# esp-12-f-breakout-ch340g.net
KiCad netlist of a schematic drawn in EAGLE
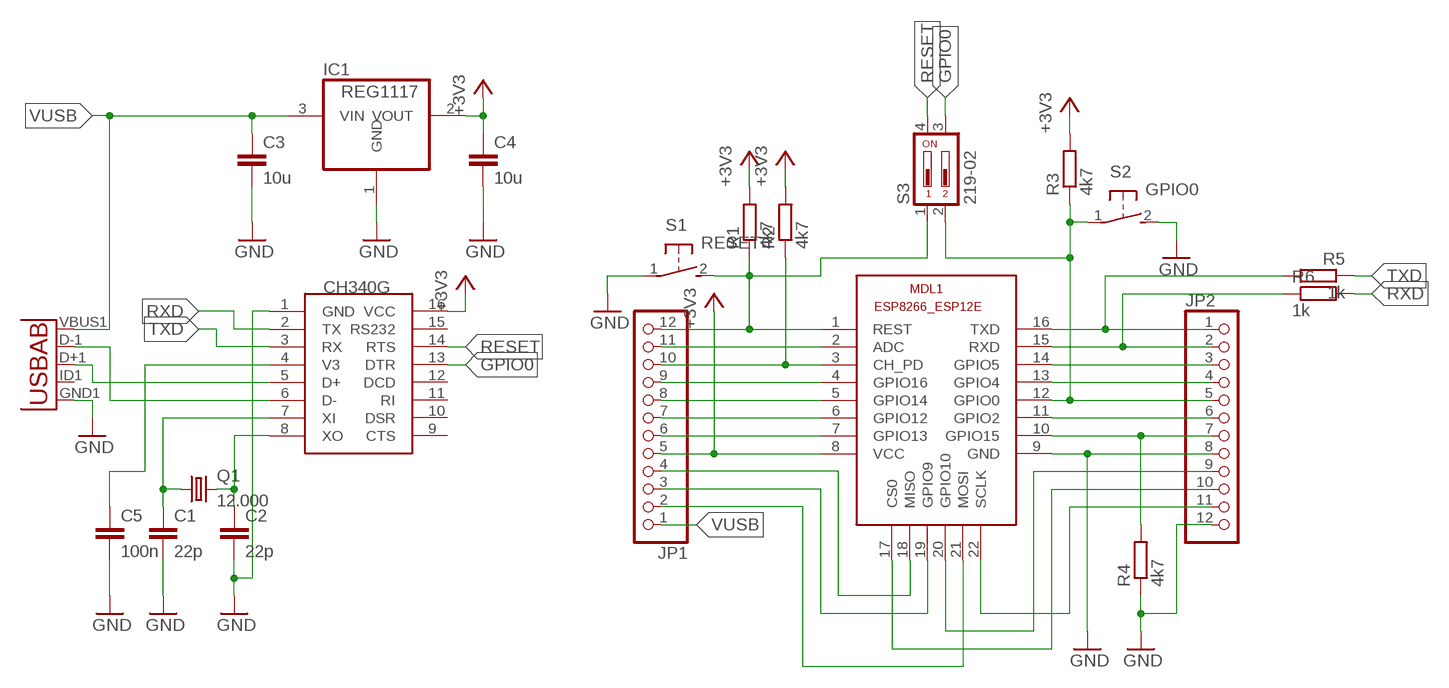
[diagram p0: schematic, sheet 1]

(export (version "E")
  (design (tool "Eeschema 10.0.6"))
  (components
    (comp (ref "C1")
      (value "22p")
      (footprint "eagle-import:C0805")
      (libsource (lib "eagle-import") (part "C-EUC0805"))
    )
    (comp (ref "C2")
      (value "22p")
      (footprint "eagle-import:C0805")
      (libsource (lib "eagle-import") (part "C-EUC0805"))
    )
    (comp (ref "C3")
      (value "10u")
      (footprint "eagle-import:C0805")
      (libsource (lib "eagle-import") (part "C-EUC0805"))
    )
    (comp (ref "C4")
      (value "10u")
      (footprint "eagle-import:C0805")
      (libsource (lib "eagle-import") (part "C-EUC0805"))
    )
    (comp (ref "C5")
      (value "100n")
      (footprint "eagle-import:C0805")
      (libsource (lib "eagle-import") (part "C-EUC0805"))
    )
    (comp (ref "IC1")
      (value "REG1117")
      (footprint "eagle-import:SOT223")
      (libsource (lib "eagle-import") (part "REG1117"))
    )
    (comp (ref "JP1")
      (value "PINHD-1X12")
      (footprint "eagle-import:1X12")
      (libsource (lib "eagle-import") (part "PINHD-1X12"))
    )
    (comp (ref "JP2")
      (value "PINHD-1X12")
      (footprint "eagle-import:1X12")
      (libsource (lib "eagle-import") (part "PINHD-1X12"))
    )
    (comp (ref "MDL1")
      (value "ESP8266-12EESP8266-ESP12E")
      (footprint "eagle-import:ESP8266-ESP12E")
      (libsource (lib "eagle-import") (part "ESP8266-12EESP8266-ESP12E"))
    )
    (comp (ref "Q1")
      (value "12.000")
      (footprint "eagle-import:HC49UP")
      (libsource (lib "eagle-import") (part "CRYSTALHC49UP"))
    )
    (comp (ref "R1")
      (value "4k7")
      (footprint "eagle-import:M0805")
      (libsource (lib "eagle-import") (part "R-EU_M0805"))
    )
    (comp (ref "R2")
      (value "4k7")
      (footprint "eagle-import:M0805")
      (libsource (lib "eagle-import") (part "R-EU_M0805"))
    )
    (comp (ref "R3")
      (value "4k7")
      (footprint "eagle-import:M0805")
      (libsource (lib "eagle-import") (part "R-EU_M0805"))
    )
    (comp (ref "R4")
      (value "4k7")
      (footprint "eagle-import:M0805")
      (libsource (lib "eagle-import") (part "R-EU_M0805"))
    )
    (comp (ref "R5")
      (value "1k")
      (footprint "eagle-import:M0805")
      (libsource (lib "eagle-import") (part "R-EU_M0805"))
    )
    (comp (ref "R6")
      (value "1k")
      (footprint "eagle-import:M0805")
      (libsource (lib "eagle-import") (part "R-EU_M0805"))
    )
    (comp (ref "S1")
      (value "RESET")
      (footprint "eagle-import:DTSM-3")
      (libsource (lib "eagle-import") (part "DTSM-3"))
    )
    (comp (ref "S2")
      (value "GPIO0")
      (footprint "eagle-import:DTSM-3")
      (libsource (lib "eagle-import") (part "DTSM-3"))
    )
    (comp (ref "S3")
      (value "219-02")
      (footprint "eagle-import:CTS-219-02")
      (libsource (lib "eagle-import") (part "219-02"))
    )
    (comp (ref "U$2")
      (value "CH340G")
      (footprint "eagle-import:SOIC16")
      (libsource (lib "eagle-import") (part "CH340G"))
    )
    (comp (ref "U2")
      (value "USB\"\"")
      (footprint "eagle-import:USB-MICRO-SMD")
      (libsource (lib "eagle-import") (part "USB{dblquote}{dblquote}"))
    )
  )
  (nets
    (net (code "1") (name "+3V3") (class "Default")
      (node (ref "C4") (pin "1") (pinfunction "1_1") (pintype "passive"))
      (node (ref "IC1") (pin "2") (pinfunction "VOUT_2") (pintype "output"))
      (node (ref "JP1") (pin "5") (pinfunction "5_5") (pintype "passive"))
      (node (ref "MDL1") (pin "8") (pinfunction "VCC_8") (pintype "bidirectional"))
      (node (ref "R1") (pin "2") (pinfunction "2_2") (pintype "passive"))
      (node (ref "R2") (pin "2") (pinfunction "2_2") (pintype "passive"))
      (node (ref "R3") (pin "2") (pinfunction "2_2") (pintype "passive"))
      (node (ref "U$2") (pin "16") (pinfunction "VCC_16") (pintype "bidirectional"))
    )
    (net (code "2") (name "GND") (class "Default")
      (node (ref "C1") (pin "2") (pinfunction "2_2") (pintype "passive"))
      (node (ref "C2") (pin "2") (pinfunction "2_2") (pintype "passive"))
      (node (ref "C3") (pin "2") (pinfunction "2_2") (pintype "passive"))
      (node (ref "C4") (pin "2") (pinfunction "2_2") (pintype "passive"))
      (node (ref "C5") (pin "2") (pinfunction "2_2") (pintype "passive"))
      (node (ref "IC1") (pin "1") (pinfunction "GND_1") (pintype "power_in"))
      (node (ref "JP2") (pin "12") (pinfunction "12_12") (pintype "passive"))
      (node (ref "JP2") (pin "8") (pinfunction "8_8") (pintype "passive"))
      (node (ref "MDL1") (pin "9") (pinfunction "GND_9") (pintype "bidirectional"))
      (node (ref "R4") (pin "1") (pinfunction "1_1") (pintype "passive"))
      (node (ref "S1") (pin "1") (pinfunction "1_1") (pintype "passive"))
      (node (ref "S2") (pin "2") (pinfunction "2_2") (pintype "passive"))
      (node (ref "U$2") (pin "1") (pinfunction "GND_1") (pintype "bidirectional"))
      (node (ref "U2") (pin "GND1") (pinfunction "GND_GND1") (pintype "bidirectional"))
    )
    (net (code "3") (name "GPIO0") (class "Default")
      (node (ref "S3") (pin "3") (pinfunction "3_3") (pintype "passive"))
      (node (ref "U$2") (pin "13") (pinfunction "DTR_13") (pintype "bidirectional"))
    )
    (net (code "4") (name "Net-(MDL1-ADC)") (class "Default")
      (node (ref "JP1") (pin "11") (pinfunction "11_11") (pintype "passive"))
      (node (ref "MDL1") (pin "2") (pinfunction "ADC_2") (pintype "bidirectional"))
    )
    (net (code "5") (name "Net-(MDL1-CH_PD)") (class "Default")
      (node (ref "JP1") (pin "10") (pinfunction "10_10") (pintype "passive"))
      (node (ref "MDL1") (pin "3") (pinfunction "CH_PD_3") (pintype "bidirectional"))
      (node (ref "R2") (pin "1") (pinfunction "1_1") (pintype "passive"))
    )
    (net (code "6") (name "Net-(MDL1-CS0)") (class "Default")
      (node (ref "JP2") (pin "10") (pinfunction "10_10") (pintype "passive"))
      (node (ref "MDL1") (pin "17") (pinfunction "CS0_17") (pintype "bidirectional"))
    )
    (net (code "7") (name "Net-(MDL1-GPIO0)") (class "Default")
      (node (ref "JP2") (pin "5") (pinfunction "5_5") (pintype "passive"))
      (node (ref "MDL1") (pin "12") (pinfunction "GPIO0_12") (pintype "bidirectional"))
      (node (ref "R3") (pin "1") (pinfunction "1_1") (pintype "passive"))
      (node (ref "S2") (pin "1") (pinfunction "1_1") (pintype "passive"))
      (node (ref "S3") (pin "2") (pinfunction "2_2") (pintype "passive"))
    )
    (net (code "8") (name "Net-(MDL1-GPIO2)") (class "Default")
      (node (ref "JP2") (pin "6") (pinfunction "6_6") (pintype "passive"))
      (node (ref "MDL1") (pin "11") (pinfunction "GPIO2_11") (pintype "bidirectional"))
    )
    (net (code "9") (name "Net-(MDL1-GPIO4)") (class "Default")
      (node (ref "JP2") (pin "4") (pinfunction "4_4") (pintype "passive"))
      (node (ref "MDL1") (pin "13") (pinfunction "GPIO4_13") (pintype "bidirectional"))
    )
    (net (code "10") (name "Net-(MDL1-GPIO5)") (class "Default")
      (node (ref "JP2") (pin "3") (pinfunction "3_3") (pintype "passive"))
      (node (ref "MDL1") (pin "14") (pinfunction "GPIO5_14") (pintype "bidirectional"))
    )
    (net (code "11") (name "Net-(MDL1-GPIO9)") (class "Default")
      (node (ref "JP1") (pin "3") (pinfunction "3_3") (pintype "passive"))
      (node (ref "MDL1") (pin "19") (pinfunction "GPIO9_19") (pintype "bidirectional"))
    )
    (net (code "12") (name "Net-(MDL1-GPIO10)") (class "Default")
      (node (ref "JP2") (pin "9") (pinfunction "9_9") (pintype "passive"))
      (node (ref "MDL1") (pin "20") (pinfunction "GPIO10_20") (pintype "bidirectional"))
    )
    (net (code "13") (name "Net-(MDL1-GPIO12)") (class "Default")
      (node (ref "JP1") (pin "7") (pinfunction "7_7") (pintype "passive"))
      (node (ref "MDL1") (pin "6") (pinfunction "GPIO12_6") (pintype "bidirectional"))
    )
    (net (code "14") (name "Net-(MDL1-GPIO13)") (class "Default")
      (node (ref "JP1") (pin "6") (pinfunction "6_6") (pintype "passive"))
      (node (ref "MDL1") (pin "7") (pinfunction "GPIO13_7") (pintype "bidirectional"))
    )
    (net (code "15") (name "Net-(MDL1-GPIO14)") (class "Default")
      (node (ref "JP1") (pin "8") (pinfunction "8_8") (pintype "passive"))
      (node (ref "MDL1") (pin "5") (pinfunction "GPIO14_5") (pintype "bidirectional"))
    )
    (net (code "16") (name "Net-(MDL1-GPIO15)") (class "Default")
      (node (ref "JP2") (pin "7") (pinfunction "7_7") (pintype "passive"))
      (node (ref "MDL1") (pin "10") (pinfunction "GPIO15_10") (pintype "bidirectional"))
      (node (ref "R4") (pin "2") (pinfunction "2_2") (pintype "passive"))
    )
    (net (code "17") (name "Net-(MDL1-GPIO16)") (class "Default")
      (node (ref "JP1") (pin "9") (pinfunction "9_9") (pintype "passive"))
      (node (ref "MDL1") (pin "4") (pinfunction "GPIO16_4") (pintype "bidirectional"))
    )
    (net (code "18") (name "Net-(MDL1-MISO)") (class "Default")
      (node (ref "JP1") (pin "4") (pinfunction "4_4") (pintype "passive"))
      (node (ref "MDL1") (pin "18") (pinfunction "MISO_18") (pintype "bidirectional"))
    )
    (net (code "19") (name "Net-(MDL1-MOSI)") (class "Default")
      (node (ref "JP1") (pin "2") (pinfunction "2_2") (pintype "passive"))
      (node (ref "MDL1") (pin "21") (pinfunction "MOSI_21") (pintype "bidirectional"))
    )
    (net (code "20") (name "Net-(MDL1-REST)") (class "Default")
      (node (ref "JP1") (pin "12") (pinfunction "12_12") (pintype "passive"))
      (node (ref "MDL1") (pin "1") (pinfunction "REST_1") (pintype "bidirectional"))
      (node (ref "R1") (pin "1") (pinfunction "1_1") (pintype "passive"))
      (node (ref "S1") (pin "2") (pinfunction "2_2") (pintype "passive"))
      (node (ref "S3") (pin "1") (pinfunction "1_1") (pintype "passive"))
    )
    (net (code "21") (name "Net-(MDL1-RXD)") (class "Default")
      (node (ref "JP2") (pin "2") (pinfunction "2_2") (pintype "passive"))
      (node (ref "MDL1") (pin "15") (pinfunction "RXD_15") (pintype "bidirectional"))
      (node (ref "R6") (pin "1") (pinfunction "1_1") (pintype "passive"))
    )
    (net (code "22") (name "Net-(MDL1-SCLK)") (class "Default")
      (node (ref "JP2") (pin "11") (pinfunction "11_11") (pintype "passive"))
      (node (ref "MDL1") (pin "22") (pinfunction "SCLK_22") (pintype "bidirectional"))
    )
    (net (code "23") (name "Net-(MDL1-TXD)") (class "Default")
      (node (ref "JP2") (pin "1") (pinfunction "1_1") (pintype "passive"))
      (node (ref "MDL1") (pin "16") (pinfunction "TXD_16") (pintype "bidirectional"))
      (node (ref "R5") (pin "2") (pinfunction "2_2") (pintype "passive"))
    )
    (net (code "24") (name "Net-(U$2-D+)") (class "Default")
      (node (ref "U$2") (pin "5") (pinfunction "D+_5") (pintype "bidirectional"))
      (node (ref "U2") (pin "D+1") (pinfunction "D+_D+1") (pintype "bidirectional"))
    )
    (net (code "25") (name "Net-(U$2-D-)") (class "Default")
      (node (ref "U$2") (pin "6") (pinfunction "D-_6") (pintype "bidirectional"))
      (node (ref "U2") (pin "D-1") (pinfunction "D-_D-1") (pintype "bidirectional"))
    )
    (net (code "26") (name "Net-(U$2-V3)") (class "Default")
      (node (ref "C5") (pin "1") (pinfunction "1_1") (pintype "passive"))
      (node (ref "U$2") (pin "4") (pinfunction "V3_4") (pintype "bidirectional"))
    )
    (net (code "27") (name "Net-(U$2-XI)") (class "Default")
      (node (ref "C1") (pin "1") (pinfunction "1_1") (pintype "passive"))
      (node (ref "Q1") (pin "1") (pinfunction "1_1") (pintype "passive"))
      (node (ref "U$2") (pin "7") (pinfunction "XI_7") (pintype "bidirectional"))
    )
    (net (code "28") (name "Net-(U$2-XO)") (class "Default")
      (node (ref "C2") (pin "1") (pinfunction "1_1") (pintype "passive"))
      (node (ref "Q1") (pin "2") (pinfunction "2_2") (pintype "passive"))
      (node (ref "U$2") (pin "8") (pinfunction "XO_8") (pintype "bidirectional"))
    )
    (net (code "29") (name "RESET") (class "Default")
      (node (ref "S3") (pin "4") (pinfunction "4_4") (pintype "passive"))
      (node (ref "U$2") (pin "14") (pinfunction "RTS_14") (pintype "bidirectional"))
    )
    (net (code "30") (name "RXD") (class "Default")
      (node (ref "R6") (pin "2") (pinfunction "2_2") (pintype "passive"))
      (node (ref "U$2") (pin "2") (pinfunction "TX_2") (pintype "bidirectional"))
    )
    (net (code "31") (name "TXD") (class "Default")
      (node (ref "R5") (pin "1") (pinfunction "1_1") (pintype "passive"))
      (node (ref "U$2") (pin "3") (pinfunction "RX_3") (pintype "bidirectional"))
    )
    (net (code "32") (name "VUSB") (class "Default")
      (node (ref "C3") (pin "1") (pinfunction "1_1") (pintype "passive"))
      (node (ref "IC1") (pin "3") (pinfunction "VIN_3") (pintype "input"))
      (node (ref "JP1") (pin "1") (pinfunction "1_1") (pintype "passive"))
      (node (ref "U2") (pin "VBUS1") (pinfunction "VBUS_VBUS1") (pintype "bidirectional"))
    )
    (net (code "33") (name "unconnected-(U$2-CTS-Pad9)") (class "Default")
      (node (ref "U$2") (pin "9") (pinfunction "CTS_9") (pintype "bidirectional"))
    )
    (net (code "34") (name "unconnected-(U$2-DCD-Pad12)") (class "Default")
      (node (ref "U$2") (pin "12") (pinfunction "DCD_12") (pintype "bidirectional"))
    )
    (net (code "35") (name "unconnected-(U$2-DSR-Pad10)") (class "Default")
      (node (ref "U$2") (pin "10") (pinfunction "DSR_10") (pintype "bidirectional"))
    )
    (net (code "36") (name "unconnected-(U$2-RI-Pad11)") (class "Default")
      (node (ref "U$2") (pin "11") (pinfunction "RI_11") (pintype "bidirectional"))
    )
    (net (code "37") (name "unconnected-(U$2-RS232-Pad15)") (class "Default")
      (node (ref "U$2") (pin "15") (pinfunction "RS232_15") (pintype "bidirectional"))
    )
    (net (code "38") (name "unconnected-(U2-USBID-PadID1)") (class "Default")
      (node (ref "U2") (pin "ID1") (pinfunction "USBID_ID1") (pintype "bidirectional"))
    )
  )
)
